# ADS1274.net
KiCad netlist of a schematic drawn in Altium Designer
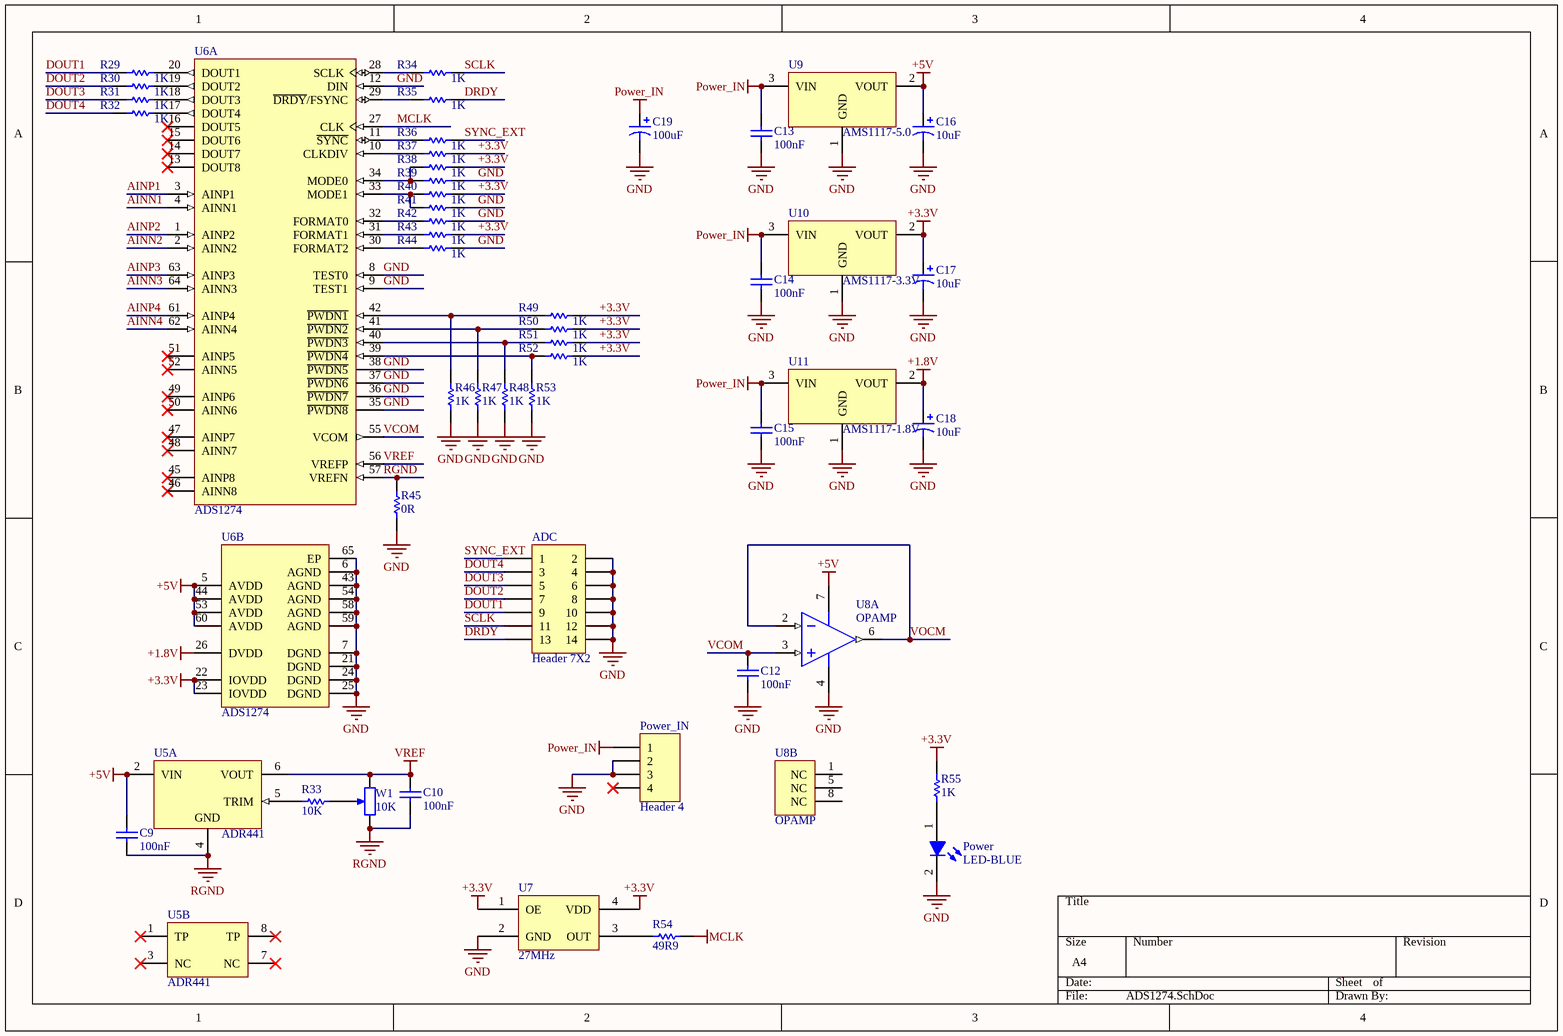
[diagram p0: ADS1274.SchDoc]

(export (version "E")
  (design (tool "Eeschema 10.0.6"))
  (components
    (comp (ref "ADC")
      (value "Header 7X2")
      (footprint "HEADER7X2")
      (description "Header, 7-Pin, Dual row")
      (fields (field (name "PUBLISHER") "Altium Limited"))
      (libsource (lib "Miscellaneous Connectors") (part "Header 7X2"))
    )
    (comp (ref "C9")
      (value "100nF")
      (footprint "CAPC0603(1608)55_M")
      (libsource (lib "Slivy's ibrary") (part "CAP"))
    )
    (comp (ref "C10")
      (value "100nF")
      (footprint "CAPC0603(1608)55_M")
      (libsource (lib "Slivy's ibrary") (part "CAP"))
    )
    (comp (ref "C12")
      (value "100nF")
      (footprint "CAPC0603(1608)55_M")
      (libsource (lib "Slivy's ibrary") (part "CAP"))
    )
    (comp (ref "C13")
      (value "100nF")
      (footprint "CAPC0603(1608)55_M")
      (libsource (lib "Slivy's ibrary") (part "CAP"))
    )
    (comp (ref "C14")
      (value "100nF")
      (footprint "CAPC0603(1608)55_M")
      (libsource (lib "Slivy's ibrary") (part "CAP"))
    )
    (comp (ref "C15")
      (value "100nF")
      (footprint "CAPC0603(1608)55_M")
      (libsource (lib "Slivy's ibrary") (part "CAP"))
    )
    (comp (ref "C16")
      (value "10uF")
      (footprint "CAPC3528")
      (libsource (lib "Slivy's ibrary") (part "CAP-Pol"))
    )
    (comp (ref "C17")
      (value "10uF")
      (footprint "CAPC3528")
      (libsource (lib "Slivy's ibrary") (part "CAP-Pol"))
    )
    (comp (ref "C18")
      (value "10uF")
      (footprint "CAPC3528")
      (libsource (lib "Slivy's ibrary") (part "CAP-Pol"))
    )
    (comp (ref "C19")
      (value "100uF")
      (footprint "CAPC7343")
      (libsource (lib "Slivy's ibrary") (part "CAP-Pol"))
    )
    (comp (ref "Power")
      (value "LED-BLUE")
      (footprint "0603LED_BLUE_V")
      (libsource (lib "Slivy's ibrary") (part "LED-BLUE"))
    )
    (comp (ref "Power_IN")
      (value "Header 4")
      (footprint "3.96-4")
      (description "Header, 4-Pin")
      (fields (field (name "PUBLISHER") "Altium Limited"))
      (libsource (lib "Miscellaneous Connectors") (part "Header 4"))
    )
    (comp (ref "R29")
      (value "1K")
      (footprint "RESC0603(1608)_M")
      (libsource (lib "Slivy's ibrary") (part "RES"))
    )
    (comp (ref "R30")
      (value "1K")
      (footprint "RESC0603(1608)_M")
      (libsource (lib "Slivy's ibrary") (part "RES"))
    )
    (comp (ref "R31")
      (value "1K")
      (footprint "RESC0603(1608)_M")
      (libsource (lib "Slivy's ibrary") (part "RES"))
    )
    (comp (ref "R32")
      (value "1K")
      (footprint "RESC0603(1608)_M")
      (libsource (lib "Slivy's ibrary") (part "RES"))
    )
    (comp (ref "R33")
      (value "10K")
      (footprint "RESC0603(1608)_M")
      (libsource (lib "Slivy's ibrary") (part "RES"))
    )
    (comp (ref "R34")
      (value "1K")
      (footprint "RESC0603(1608)_M")
      (libsource (lib "Slivy's ibrary") (part "RES"))
    )
    (comp (ref "R35")
      (value "1K")
      (footprint "RESC0603(1608)_M")
      (libsource (lib "Slivy's ibrary") (part "RES"))
    )
    (comp (ref "R36")
      (value "1K")
      (footprint "RESC0603(1608)_M")
      (libsource (lib "Slivy's ibrary") (part "RES"))
    )
    (comp (ref "R37")
      (value "1K")
      (footprint "RESC0603(1608)_M")
      (libsource (lib "Slivy's ibrary") (part "RES"))
    )
    (comp (ref "R38")
      (value "1K")
      (footprint "RESC0603(1608)_M")
      (libsource (lib "Slivy's ibrary") (part "RES"))
    )
    (comp (ref "R39")
      (value "1K")
      (footprint "RESC0603(1608)_M")
      (libsource (lib "Slivy's ibrary") (part "RES"))
    )
    (comp (ref "R40")
      (value "1K")
      (footprint "RESC0603(1608)_M")
      (libsource (lib "Slivy's ibrary") (part "RES"))
    )
    (comp (ref "R41")
      (value "1K")
      (footprint "RESC0603(1608)_M")
      (libsource (lib "Slivy's ibrary") (part "RES"))
    )
    (comp (ref "R42")
      (value "1K")
      (footprint "RESC0603(1608)_M")
      (libsource (lib "Slivy's ibrary") (part "RES"))
    )
    (comp (ref "R43")
      (value "1K")
      (footprint "RESC0603(1608)_M")
      (libsource (lib "Slivy's ibrary") (part "RES"))
    )
    (comp (ref "R44")
      (value "1K")
      (footprint "RESC0603(1608)_M")
      (libsource (lib "Slivy's ibrary") (part "RES"))
    )
    (comp (ref "R45")
      (value "0R")
      (footprint "RESC0603(1608)_M")
      (libsource (lib "Slivy's ibrary") (part "RES"))
    )
    (comp (ref "R46")
      (value "1K")
      (footprint "RESC0603(1608)_M")
      (libsource (lib "Slivy's ibrary") (part "RES"))
    )
    (comp (ref "R47")
      (value "1K")
      (footprint "RESC0603(1608)_M")
      (libsource (lib "Slivy's ibrary") (part "RES"))
    )
    (comp (ref "R48")
      (value "1K")
      (footprint "RESC0603(1608)_M")
      (libsource (lib "Slivy's ibrary") (part "RES"))
    )
    (comp (ref "R49")
      (value "1K")
      (footprint "RESC0603(1608)_M")
      (libsource (lib "Slivy's ibrary") (part "RES"))
    )
    (comp (ref "R50")
      (value "1K")
      (footprint "RESC0603(1608)_M")
      (libsource (lib "Slivy's ibrary") (part "RES"))
    )
    (comp (ref "R51")
      (value "1K")
      (footprint "RESC0603(1608)_M")
      (libsource (lib "Slivy's ibrary") (part "RES"))
    )
    (comp (ref "R52")
      (value "1K")
      (footprint "RESC0603(1608)_M")
      (libsource (lib "Slivy's ibrary") (part "RES"))
    )
    (comp (ref "R53")
      (value "1K")
      (footprint "RESC0603(1608)_M")
      (libsource (lib "Slivy's ibrary") (part "RES"))
    )
    (comp (ref "R54")
      (value "49R9")
      (footprint "RESC0603(1608)_M")
      (libsource (lib "Slivy's ibrary") (part "RES"))
    )
    (comp (ref "R55")
      (value "1K")
      (footprint "RESC0603(1608)_M")
      (libsource (lib "Slivy's ibrary") (part "RES"))
    )
    (comp (ref "U5") (value "ADR441") (footprint "SOIC8") (libsource (lib "Slivy's ibrary") (part "ADR421")))
    (comp (ref "U6")
      (value "ADS1274")
      (footprint "EQFP64")
      (libsource (lib "Slivy's ibrary") (part "ADS1274"))
    )
    (comp (ref "U7")
      (value "27MHz")
      (footprint "SMD7050")
      (libsource (lib "Integrated_Library1") (part "OSC7050"))
    )
    (comp (ref "U8") (value "OPAMP") (footprint "SOIC8") (libsource (lib "Slivy's ibrary") (part "OPAMP")))
    (comp (ref "U9")
      (value "AMS1117-5.0")
      (footprint "SOT-223_M")
      (libsource (lib "Slivy's ibrary") (part "AMS1117"))
    )
    (comp (ref "U10")
      (value "AMS1117-3.3V")
      (footprint "SOT-223_M")
      (libsource (lib "Slivy's ibrary") (part "AMS1117"))
    )
    (comp (ref "U11")
      (value "AMS1117-1.8V")
      (footprint "SOT-223_M")
      (libsource (lib "Slivy's ibrary") (part "AMS1117"))
    )
    (comp (ref "W1")
      (value "10K")
      (footprint "VR5")
      (description "Potentiometer")
      (fields
        (field (name "MANUFACTURER") "Generic Components")
        (field (name "PUBLISHER") "Altium Hobart Technology Centre")
      )
      (libsource (lib "Integrated_Library1") (part "RPot2"))
    )
  )
  (nets
    (net (code "1") (name "+1.8V") (class "Default")
      (node (ref "C18") (pin "1") (pinfunction "1_1") (pintype "passive"))
      (node (ref "U11") (pin "2") (pinfunction "VOUT_2") (pintype "power_in"))
      (node (ref "U6") (pin "26") (pinfunction "DVDD_26") (pintype "power_in"))
    )
    (net (code "2") (name "+3.3V") (class "Default")
      (node (ref "C17") (pin "1") (pinfunction "1_1") (pintype "passive"))
      (node (ref "R37") (pin "2") (pinfunction "2_2") (pintype "passive"))
      (node (ref "R38") (pin "2") (pinfunction "2_2") (pintype "passive"))
      (node (ref "R40") (pin "2") (pinfunction "2_2") (pintype "passive"))
      (node (ref "R43") (pin "2") (pinfunction "2_2") (pintype "passive"))
      (node (ref "R49") (pin "2") (pinfunction "2_2") (pintype "passive"))
      (node (ref "R50") (pin "2") (pinfunction "2_2") (pintype "passive"))
      (node (ref "R51") (pin "2") (pinfunction "2_2") (pintype "passive"))
      (node (ref "R52") (pin "2") (pinfunction "2_2") (pintype "passive"))
      (node (ref "R55") (pin "2") (pinfunction "2_2") (pintype "passive"))
      (node (ref "U10") (pin "2") (pinfunction "VOUT_2") (pintype "power_in"))
      (node (ref "U6") (pin "22") (pinfunction "IOVDD_22") (pintype "power_in"))
      (node (ref "U6") (pin "23") (pinfunction "IOVDD_23") (pintype "power_in"))
      (node (ref "U7") (pin "1") (pinfunction "OE_1") (pintype "passive"))
      (node (ref "U7") (pin "4") (pinfunction "VDD_4") (pintype "passive"))
    )
    (net (code "3") (name "+5V") (class "Default")
      (node (ref "C16") (pin "1") (pinfunction "1_1") (pintype "passive"))
      (node (ref "C9") (pin "2") (pinfunction "2_2") (pintype "passive"))
      (node (ref "U5") (pin "2") (pinfunction "VIN_2") (pintype "power_in"))
      (node (ref "U6") (pin "44") (pinfunction "AVDD_44") (pintype "power_in"))
      (node (ref "U6") (pin "5") (pinfunction "AVDD_5") (pintype "power_in"))
      (node (ref "U6") (pin "53") (pinfunction "AVDD_53") (pintype "power_in"))
      (node (ref "U6") (pin "60") (pinfunction "AVDD_60") (pintype "power_in"))
      (node (ref "U8") (pin "7") (pinfunction "V+_7") (pintype "power_in"))
      (node (ref "U9") (pin "2") (pinfunction "VOUT_2") (pintype "power_in"))
    )
    (net (code "4") (name "/AINN1") (class "Default")
      (node (ref "U6") (pin "4") (pinfunction "AINN1_4") (pintype "input"))
    )
    (net (code "5") (name "/AINN2") (class "Default")
      (node (ref "U6") (pin "2") (pinfunction "AINN2_2") (pintype "input"))
    )
    (net (code "6") (name "/AINN3") (class "Default")
      (node (ref "U6") (pin "64") (pinfunction "AINN3_64") (pintype "input"))
    )
    (net (code "7") (name "/AINN4") (class "Default")
      (node (ref "U6") (pin "62") (pinfunction "AINN4_62") (pintype "input"))
    )
    (net (code "8") (name "/AINP1") (class "Default")
      (node (ref "U6") (pin "3") (pinfunction "AINP1_3") (pintype "input"))
    )
    (net (code "9") (name "/AINP2") (class "Default")
      (node (ref "U6") (pin "1") (pinfunction "AINP2_1") (pintype "input"))
    )
    (net (code "10") (name "/AINP3") (class "Default")
      (node (ref "U6") (pin "63") (pinfunction "AINP3_63") (pintype "input"))
    )
    (net (code "11") (name "/AINP4") (class "Default")
      (node (ref "U6") (pin "61") (pinfunction "AINP4_61") (pintype "input"))
    )
    (net (code "12") (name "/DOUT1") (class "Default")
      (node (ref "ADC") (pin "9") (pinfunction "9_9") (pintype "passive"))
      (node (ref "R29") (pin "1") (pinfunction "1_1") (pintype "passive"))
    )
    (net (code "13") (name "/DOUT2") (class "Default")
      (node (ref "ADC") (pin "7") (pinfunction "7_7") (pintype "passive"))
      (node (ref "R30") (pin "1") (pinfunction "1_1") (pintype "passive"))
    )
    (net (code "14") (name "/DOUT3") (class "Default")
      (node (ref "ADC") (pin "5") (pinfunction "5_5") (pintype "passive"))
      (node (ref "R31") (pin "1") (pinfunction "1_1") (pintype "passive"))
    )
    (net (code "15") (name "/DOUT4") (class "Default")
      (node (ref "ADC") (pin "3") (pinfunction "3_3") (pintype "passive"))
      (node (ref "R32") (pin "1") (pinfunction "1_1") (pintype "passive"))
    )
    (net (code "16") (name "/DRDY") (class "Default")
      (node (ref "ADC") (pin "13") (pinfunction "13_13") (pintype "passive"))
      (node (ref "R35") (pin "2") (pinfunction "2_2") (pintype "passive"))
    )
    (net (code "17") (name "/SCLK") (class "Default")
      (node (ref "ADC") (pin "11") (pinfunction "11_11") (pintype "passive"))
      (node (ref "R34") (pin "2") (pinfunction "2_2") (pintype "passive"))
    )
    (net (code "18") (name "/SYNC_EXT") (class "Default")
      (node (ref "ADC") (pin "1") (pinfunction "1_1") (pintype "passive"))
      (node (ref "R36") (pin "2") (pinfunction "2_2") (pintype "passive"))
    )
    (net (code "19") (name "/VCOM") (class "Default")
      (node (ref "C12") (pin "2") (pinfunction "2_2") (pintype "passive"))
      (node (ref "U6") (pin "55") (pinfunction "VCOM_55") (pintype "output"))
      (node (ref "U8") (pin "3") (pinfunction "IN+_3") (pintype "input"))
    )
    (net (code "20") (name "/VOCM") (class "Default")
      (node (ref "U8") (pin "2") (pinfunction "IN-_2") (pintype "input"))
      (node (ref "U8") (pin "6") (pinfunction "OUT_6") (pintype "output"))
    )
    (net (code "21") (name "GND") (class "Default")
      (node (ref "ADC") (pin "10") (pinfunction "10_10") (pintype "passive"))
      (node (ref "ADC") (pin "12") (pinfunction "12_12") (pintype "passive"))
      (node (ref "ADC") (pin "14") (pinfunction "14_14") (pintype "passive"))
      (node (ref "ADC") (pin "2") (pinfunction "2_2") (pintype "passive"))
      (node (ref "ADC") (pin "4") (pinfunction "4_4") (pintype "passive"))
      (node (ref "ADC") (pin "6") (pinfunction "6_6") (pintype "passive"))
      (node (ref "ADC") (pin "8") (pinfunction "8_8") (pintype "passive"))
      (node (ref "C12") (pin "1") (pinfunction "1_1") (pintype "passive"))
      (node (ref "C13") (pin "1") (pinfunction "1_1") (pintype "passive"))
      (node (ref "C14") (pin "1") (pinfunction "1_1") (pintype "passive"))
      (node (ref "C15") (pin "1") (pinfunction "1_1") (pintype "passive"))
      (node (ref "C16") (pin "2") (pinfunction "2_2") (pintype "passive"))
      (node (ref "C17") (pin "2") (pinfunction "2_2") (pintype "passive"))
      (node (ref "C18") (pin "2") (pinfunction "2_2") (pintype "passive"))
      (node (ref "C19") (pin "2") (pinfunction "2_2") (pintype "passive"))
      (node (ref "Power") (pin "2") (pinfunction "K_2") (pintype "passive"))
      (node (ref "Power_IN") (pin "2") (pinfunction "2_2") (pintype "passive"))
      (node (ref "Power_IN") (pin "3") (pinfunction "3_3") (pintype "passive"))
      (node (ref "R39") (pin "2") (pinfunction "2_2") (pintype "passive"))
      (node (ref "R41") (pin "2") (pinfunction "2_2") (pintype "passive"))
      (node (ref "R42") (pin "2") (pinfunction "2_2") (pintype "passive"))
      (node (ref "R44") (pin "2") (pinfunction "2_2") (pintype "passive"))
      (node (ref "R45") (pin "1") (pinfunction "1_1") (pintype "passive"))
      (node (ref "R46") (pin "1") (pinfunction "1_1") (pintype "passive"))
      (node (ref "R47") (pin "1") (pinfunction "1_1") (pintype "passive"))
      (node (ref "R48") (pin "1") (pinfunction "1_1") (pintype "passive"))
      (node (ref "R53") (pin "1") (pinfunction "1_1") (pintype "passive"))
      (node (ref "U10") (pin "1") (pinfunction "GND_1") (pintype "power_in"))
      (node (ref "U11") (pin "1") (pinfunction "GND_1") (pintype "power_in"))
      (node (ref "U6") (pin "12") (pinfunction "DIN_12") (pintype "input"))
      (node (ref "U6") (pin "21") (pinfunction "DGND_21") (pintype "power_in"))
      (node (ref "U6") (pin "24") (pinfunction "DGND_24") (pintype "power_in"))
      (node (ref "U6") (pin "25") (pinfunction "DGND_25") (pintype "power_in"))
      (node (ref "U6") (pin "35") (pinfunction "~{PWDN8}_35") (pintype "passive"))
      (node (ref "U6") (pin "36") (pinfunction "~{PWDN7}_36") (pintype "passive"))
      (node (ref "U6") (pin "37") (pinfunction "~{PWDN6}_37") (pintype "passive"))
      (node (ref "U6") (pin "38") (pinfunction "~{PWDN5}_38") (pintype "passive"))
      (node (ref "U6") (pin "43") (pinfunction "AGND_43") (pintype "power_in"))
      (node (ref "U6") (pin "54") (pinfunction "AGND_54") (pintype "power_in"))
      (node (ref "U6") (pin "58") (pinfunction "AGND_58") (pintype "power_in"))
      (node (ref "U6") (pin "59") (pinfunction "AGND_59") (pintype "power_in"))
      (node (ref "U6") (pin "6") (pinfunction "AGND_6") (pintype "power_in"))
      (node (ref "U6") (pin "65") (pinfunction "EP_65") (pintype "passive"))
      (node (ref "U6") (pin "7") (pinfunction "DGND_7") (pintype "power_in"))
      (node (ref "U6") (pin "8") (pinfunction "TEST0_8") (pintype "input"))
      (node (ref "U6") (pin "9") (pinfunction "TEST1_9") (pintype "input"))
      (node (ref "U7") (pin "2") (pinfunction "GND_2") (pintype "passive"))
      (node (ref "U8") (pin "4") (pinfunction "V-_4") (pintype "power_in"))
      (node (ref "U9") (pin "1") (pinfunction "GND_1") (pintype "power_in"))
    )
    (net (code "22") (name "MCLK") (class "Default")
      (node (ref "R54") (pin "2") (pinfunction "2_2") (pintype "passive"))
      (node (ref "U6") (pin "27") (pinfunction "CLK_27") (pintype "input"))
    )
    (net (code "23") (name "Net-(Power-A)") (class "Default")
      (node (ref "Power") (pin "1") (pinfunction "A_1") (pintype "passive"))
      (node (ref "R55") (pin "1") (pinfunction "1_1") (pintype "passive"))
    )
    (net (code "24") (name "Net-(U5A-TRIM)") (class "Default")
      (node (ref "R33") (pin "1") (pinfunction "1_1") (pintype "passive"))
      (node (ref "U5") (pin "5") (pinfunction "TRIM_5") (pintype "input"))
    )
    (net (code "25") (name "Net-(U6A-CLKDIV)") (class "Default")
      (node (ref "R37") (pin "1") (pinfunction "1_1") (pintype "passive"))
      (node (ref "U6") (pin "10") (pinfunction "CLKDIV_10") (pintype "input"))
    )
    (net (code "26") (name "Net-(U6A-DOUT1)") (class "Default")
      (node (ref "R29") (pin "2") (pinfunction "2_2") (pintype "passive"))
      (node (ref "U6") (pin "20") (pinfunction "DOUT1_20") (pintype "output"))
    )
    (net (code "27") (name "Net-(U6A-DOUT2)") (class "Default")
      (node (ref "R30") (pin "2") (pinfunction "2_2") (pintype "passive"))
      (node (ref "U6") (pin "19") (pinfunction "DOUT2_19") (pintype "output"))
    )
    (net (code "28") (name "Net-(U6A-DOUT3)") (class "Default")
      (node (ref "R31") (pin "2") (pinfunction "2_2") (pintype "passive"))
      (node (ref "U6") (pin "18") (pinfunction "DOUT3_18") (pintype "output"))
    )
    (net (code "29") (name "Net-(U6A-DOUT4)") (class "Default")
      (node (ref "R32") (pin "2") (pinfunction "2_2") (pintype "passive"))
      (node (ref "U6") (pin "17") (pinfunction "DOUT4_17") (pintype "output"))
    )
    (net (code "30") (name "Net-(U6A-FORMAT0)") (class "Default")
      (node (ref "R42") (pin "1") (pinfunction "1_1") (pintype "passive"))
      (node (ref "U6") (pin "32") (pinfunction "FORMAT0_32") (pintype "input"))
    )
    (net (code "31") (name "Net-(U6A-FORMAT1)") (class "Default")
      (node (ref "R43") (pin "1") (pinfunction "1_1") (pintype "passive"))
      (node (ref "U6") (pin "31") (pinfunction "FORMAT1_31") (pintype "input"))
    )
    (net (code "32") (name "Net-(U6A-FORMAT2)") (class "Default")
      (node (ref "R44") (pin "1") (pinfunction "1_1") (pintype "passive"))
      (node (ref "U6") (pin "30") (pinfunction "FORMAT2_30") (pintype "input"))
    )
    (net (code "33") (name "Net-(U6A-MODE0)") (class "Default")
      (node (ref "R38") (pin "1") (pinfunction "1_1") (pintype "passive"))
      (node (ref "R39") (pin "1") (pinfunction "1_1") (pintype "passive"))
      (node (ref "U6") (pin "34") (pinfunction "MODE0_34") (pintype "input"))
    )
    (net (code "34") (name "Net-(U6A-MODE1)") (class "Default")
      (node (ref "R40") (pin "1") (pinfunction "1_1") (pintype "passive"))
      (node (ref "R41") (pin "1") (pinfunction "1_1") (pintype "passive"))
      (node (ref "U6") (pin "33") (pinfunction "MODE1_33") (pintype "input"))
    )
    (net (code "35") (name "Net-(U6A-SCLK)") (class "Default")
      (node (ref "R34") (pin "1") (pinfunction "1_1") (pintype "passive"))
      (node (ref "U6") (pin "28") (pinfunction "SCLK_28") (pintype "bidirectional"))
    )
    (net (code "36") (name "Net-(U6A-~{DRDY}{slash}FSYNC)") (class "Default")
      (node (ref "R35") (pin "1") (pinfunction "1_1") (pintype "passive"))
      (node (ref "U6") (pin "29") (pinfunction "~{DRDY}/FSYNC_29") (pintype "bidirectional"))
    )
    (net (code "37") (name "Net-(U6A-~{PWDN1})") (class "Default")
      (node (ref "R46") (pin "2") (pinfunction "2_2") (pintype "passive"))
      (node (ref "R49") (pin "1") (pinfunction "1_1") (pintype "passive"))
      (node (ref "U6") (pin "42") (pinfunction "~{PWDN1}_42") (pintype "input"))
    )
    (net (code "38") (name "Net-(U6A-~{PWDN2})") (class "Default")
      (node (ref "R47") (pin "2") (pinfunction "2_2") (pintype "passive"))
      (node (ref "R50") (pin "1") (pinfunction "1_1") (pintype "passive"))
      (node (ref "U6") (pin "41") (pinfunction "~{PWDN2}_41") (pintype "input"))
    )
    (net (code "39") (name "Net-(U6A-~{PWDN3})") (class "Default")
      (node (ref "R48") (pin "2") (pinfunction "2_2") (pintype "passive"))
      (node (ref "R51") (pin "1") (pinfunction "1_1") (pintype "passive"))
      (node (ref "U6") (pin "40") (pinfunction "~{PWDN3}_40") (pintype "input"))
    )
    (net (code "40") (name "Net-(U6A-~{PWDN4})") (class "Default")
      (node (ref "R52") (pin "1") (pinfunction "1_1") (pintype "passive"))
      (node (ref "R53") (pin "2") (pinfunction "2_2") (pintype "passive"))
      (node (ref "U6") (pin "39") (pinfunction "~{PWDN4}_39") (pintype "input"))
    )
    (net (code "41") (name "Net-(U6A-~{SYNC})") (class "Default")
      (node (ref "R36") (pin "1") (pinfunction "1_1") (pintype "passive"))
      (node (ref "U6") (pin "11") (pinfunction "~{SYNC}_11") (pintype "bidirectional"))
    )
    (net (code "42") (name "Net-(U7-OUT)") (class "Default")
      (node (ref "R54") (pin "1") (pinfunction "1_1") (pintype "passive"))
      (node (ref "U7") (pin "3") (pinfunction "OUT_3") (pintype "passive"))
    )
    (net (code "43") (name "Net-(W1-TAP)") (class "Default")
      (node (ref "R33") (pin "2") (pinfunction "2_2") (pintype "passive"))
      (node (ref "W1") (pin "2") (pinfunction "TAP_2") (pintype "passive"))
    )
    (net (code "44") (name "Power_IN") (class "Default")
      (node (ref "C13") (pin "2") (pinfunction "2_2") (pintype "passive"))
      (node (ref "C14") (pin "2") (pinfunction "2_2") (pintype "passive"))
      (node (ref "C15") (pin "2") (pinfunction "2_2") (pintype "passive"))
      (node (ref "C19") (pin "1") (pinfunction "1_1") (pintype "passive"))
      (node (ref "Power_IN") (pin "1") (pinfunction "1_1") (pintype "passive"))
      (node (ref "U10") (pin "3") (pinfunction "VIN_3") (pintype "power_in"))
      (node (ref "U11") (pin "3") (pinfunction "VIN_3") (pintype "power_in"))
      (node (ref "U9") (pin "3") (pinfunction "VIN_3") (pintype "power_in"))
    )
    (net (code "45") (name "RGND") (class "Default")
      (node (ref "C10") (pin "1") (pinfunction "1_1") (pintype "passive"))
      (node (ref "C9") (pin "1") (pinfunction "1_1") (pintype "passive"))
      (node (ref "R45") (pin "2") (pinfunction "2_2") (pintype "passive"))
      (node (ref "U5") (pin "4") (pinfunction "GND_4") (pintype "power_in"))
      (node (ref "U6") (pin "57") (pinfunction "VREFN_57") (pintype "input"))
      (node (ref "W1") (pin "3") (pinfunction "BOT_3") (pintype "passive"))
    )
    (net (code "46") (name "VREF") (class "Default")
      (node (ref "C10") (pin "2") (pinfunction "2_2") (pintype "passive"))
      (node (ref "U5") (pin "6") (pinfunction "VOUT_6") (pintype "power_in"))
      (node (ref "U6") (pin "56") (pinfunction "VREFP_56") (pintype "input"))
      (node (ref "W1") (pin "1") (pinfunction "TOP_1") (pintype "passive"))
    )
    (net (code "47") (name "unconnected-(Power_IN-Pad4)") (class "Default")
      (node (ref "Power_IN") (pin "4") (pinfunction "4_4") (pintype "passive+no_connect"))
    )
    (net (code "48") (name "unconnected-(U5B-NC-Pad3)") (class "Default")
      (node (ref "U5") (pin "3") (pinfunction "NC_3") (pintype "passive+no_connect"))
    )
    (net (code "49") (name "unconnected-(U5B-NC-Pad7)") (class "Default")
      (node (ref "U5") (pin "7") (pinfunction "NC_7") (pintype "passive+no_connect"))
    )
    (net (code "50") (name "unconnected-(U5B-TP-Pad1)") (class "Default")
      (node (ref "U5") (pin "1") (pinfunction "TP_1") (pintype "passive+no_connect"))
    )
    (net (code "51") (name "unconnected-(U5B-TP-Pad8)") (class "Default")
      (node (ref "U5") (pin "8") (pinfunction "TP_8") (pintype "passive+no_connect"))
    )
    (net (code "52") (name "unconnected-(U6A-AINN5-Pad52)") (class "Default")
      (node (ref "U6") (pin "52") (pinfunction "AINN5_52") (pintype "passive+no_connect"))
    )
    (net (code "53") (name "unconnected-(U6A-AINN6-Pad50)") (class "Default")
      (node (ref "U6") (pin "50") (pinfunction "AINN6_50") (pintype "passive+no_connect"))
    )
    (net (code "54") (name "unconnected-(U6A-AINN7-Pad48)") (class "Default")
      (node (ref "U6") (pin "48") (pinfunction "AINN7_48") (pintype "passive+no_connect"))
    )
    (net (code "55") (name "unconnected-(U6A-AINN8-Pad46)") (class "Default")
      (node (ref "U6") (pin "46") (pinfunction "AINN8_46") (pintype "passive+no_connect"))
    )
    (net (code "56") (name "unconnected-(U6A-AINP5-Pad51)") (class "Default")
      (node (ref "U6") (pin "51") (pinfunction "AINP5_51") (pintype "passive+no_connect"))
    )
    (net (code "57") (name "unconnected-(U6A-AINP6-Pad49)") (class "Default")
      (node (ref "U6") (pin "49") (pinfunction "AINP6_49") (pintype "passive+no_connect"))
    )
    (net (code "58") (name "unconnected-(U6A-AINP7-Pad47)") (class "Default")
      (node (ref "U6") (pin "47") (pinfunction "AINP7_47") (pintype "passive+no_connect"))
    )
    (net (code "59") (name "unconnected-(U6A-AINP8-Pad45)") (class "Default")
      (node (ref "U6") (pin "45") (pinfunction "AINP8_45") (pintype "passive+no_connect"))
    )
    (net (code "60") (name "unconnected-(U6A-DOUT5-Pad16)") (class "Default")
      (node (ref "U6") (pin "16") (pinfunction "DOUT5_16") (pintype "passive+no_connect"))
    )
    (net (code "61") (name "unconnected-(U6A-DOUT6-Pad15)") (class "Default")
      (node (ref "U6") (pin "15") (pinfunction "DOUT6_15") (pintype "passive+no_connect"))
    )
    (net (code "62") (name "unconnected-(U6A-DOUT7-Pad14)") (class "Default")
      (node (ref "U6") (pin "14") (pinfunction "DOUT7_14") (pintype "passive+no_connect"))
    )
    (net (code "63") (name "unconnected-(U6A-DOUT8-Pad13)") (class "Default")
      (node (ref "U6") (pin "13") (pinfunction "DOUT8_13") (pintype "passive+no_connect"))
    )
    (net (code "64") (name "unconnected-(U8B-NC-Pad1)") (class "Default")
      (node (ref "U8") (pin "1") (pinfunction "NC_1") (pintype "passive"))
    )
    (net (code "65") (name "unconnected-(U8B-NC-Pad5)") (class "Default")
      (node (ref "U8") (pin "5") (pinfunction "NC_5") (pintype "passive"))
    )
    (net (code "66") (name "unconnected-(U8B-NC-Pad8)") (class "Default")
      (node (ref "U8") (pin "8") (pinfunction "NC_8") (pintype "passive"))
    )
  )
)
